# Power_section.net
KiCad netlist of a schematic drawn in Altium Designer
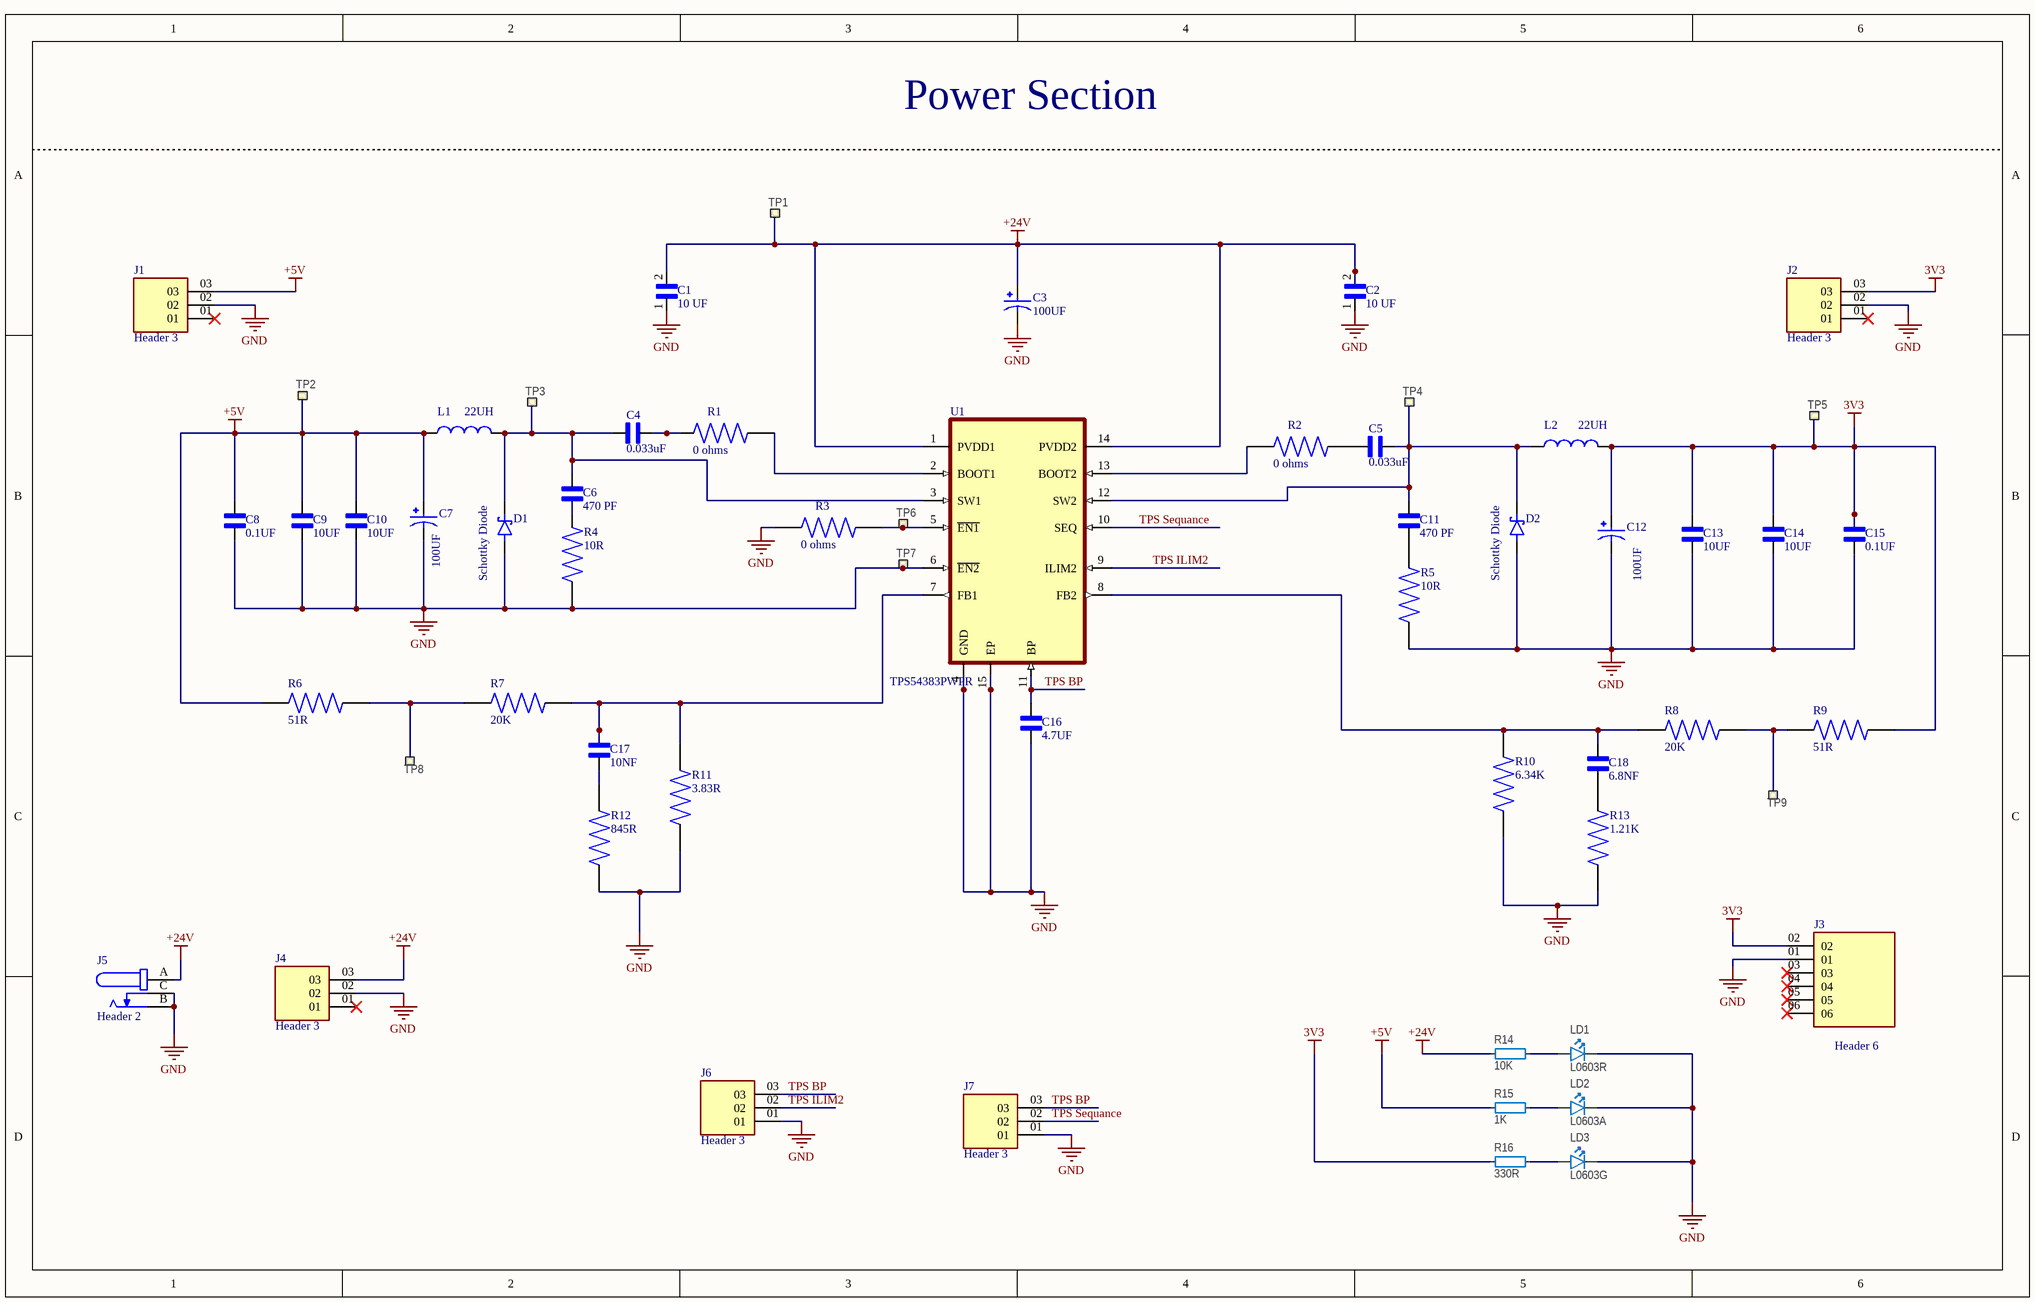
[diagram p0: Power section.SchDoc]

(export (version "E")
  (design (tool "Eeschema 10.0.6"))
  (components
    (comp (ref "C1")
      (value "10 UF")
      (footprint "CAPC3216X180N")
      (description "CAP CER 10UF 16V X5R 1206")
      (fields (field (name "MF") "TDK") (field (name "DIGI-KEY_PART_NUMBER") "445-7708-2-ND"))
      (libsource (lib "C3216X5R1E106M160AB") (part "C3216X5R1E106M160AB"))
    )
    (comp (ref "C2")
      (value "10 UF")
      (footprint "CAPC3216X180N")
      (description "CAP CER 10UF 16V X5R 1206")
      (fields (field (name "MF") "TDK") (field (name "DIGI-KEY_PART_NUMBER") "445-7708-2-ND"))
      (libsource (lib "C3216X5R1E106M160AB") (part "C3216X5R1E106M160AB"))
    )
    (comp (ref "C3")
      (value "100UF")
      (footprint "CAP_EEEFC1E101P")
      (description "Capacitor, aluminum, 25 V, ±20%, 100 μF, 0.328 x 0.390\r\ninch")
      (fields (field (name "MF") "Panasonic") (field (name "MP") "EEE-FC1E101P"))
      (libsource (lib "EEEFC1E101P") (part "EEEFC1E101P"))
    )
    (comp (ref "C4")
      (value "0.033uF")
      (footprint "CAPC1608X90")
      (description "Capacitor, ceramic, 25 V, X7R, 20%, .033 μF, 0603")
      (fields (field (name "MF") "KEMET") (field (name "MP") "C0603C104J3RACTU"))
      (libsource (lib "") (part "C0603C104J3RACTU_1"))
    )
    (comp (ref "C5")
      (value "0.033uF")
      (footprint "CAPC1608X90")
      (description "Capacitor, ceramic, 25 V, X7R, 20%, .033 μF, 0603")
      (fields (field (name "MF") "KEMET") (field (name "MP") "C0603C104J3RACTU"))
      (libsource (lib "") (part "C0603C104J3RACTU_1"))
    )
    (comp (ref "C6")
      (value "470 PF")
      (footprint "CAPC1608X90")
      (description "Capacitor, ceramic, 25 V, X7R, 20%, 470 pF, 0603")
      (fields (field (name "MF") "KEMET") (field (name "MP") "C0603C104J3RACTU"))
      (libsource (lib "Accelo Integrated_Library") (part "C0603C104J3RACTU"))
    )
    (comp (ref "C7")
      (value "100UF")
      (footprint "CAP_EEEFC1E101P")
      (description "Capacitor, aluminum, 10 V, 20%, FC series, 100 μF,\r\n0.335 x 0.374")
      (fields (field (name "MF") "Panasonic") (field (name "MP") "EEE-FC1E101P"))
      (libsource (lib "EEEFC1E101P") (part "EEEFC1E101P"))
    )
    (comp (ref "C8")
      (value "0.1UF")
      (footprint "CAPC1608X90")
      (description "Capacitor, ceramic, 10 V, X7R, 20%, 0.1 μF, 0603")
      (fields (field (name "MF") "KEMET") (field (name "MP") "C0603C104J3RACTU"))
      (libsource (lib "Accelo Integrated_Library") (part "C0603C104J3RACTU"))
    )
    (comp (ref "C9")
      (value "10UF")
      (footprint "CAPC2012X140N")
      (description "Capacitor, ceramic, 6.3 V, X5R, 20%, 10 μF, 0805")
      (fields (field (name "MF") "AVX") (field (name "MP") "0805ZD474MAT2A"))
      (libsource (lib "0805ZD474MAT2A") (part "0805ZD474MAT2A"))
    )
    (comp (ref "C10")
      (value "10UF")
      (footprint "CAPC2012X140N")
      (description "Capacitor, ceramic, 6.3 V, X5R, 20%, 10 μF, 0805")
      (fields (field (name "MF") "AVX") (field (name "MP") "0805ZD474MAT2A"))
      (libsource (lib "0805ZD474MAT2A") (part "0805ZD474MAT2A"))
    )
    (comp (ref "C11")
      (value "470 PF")
      (footprint "CAPC1608X90")
      (description "Capacitor, ceramic, 25 V, X7R, 20%, 470 pF, 0603")
      (fields (field (name "MF") "KEMET") (field (name "MP") "C0603C104J3RACTU"))
      (libsource (lib "Accelo Integrated_Library") (part "C0603C104J3RACTU"))
    )
    (comp (ref "C12")
      (value "100UF")
      (footprint "CAP_EEEFC1E101P")
      (description "Capacitor, aluminum, 10 V, 20%, FC series, 100 μF,\r\n0.335 x 0.374")
      (fields (field (name "MF") "Panasonic") (field (name "MP") "EEE-FC1E101P"))
      (libsource (lib "EEEFC1E101P") (part "EEEFC1E101P"))
    )
    (comp (ref "C13")
      (value "10UF")
      (footprint "CAPC2012X140N")
      (description "Capacitor, ceramic, 6.3 V, X5R, 20%, 10 μF, 0805")
      (fields (field (name "MF") "AVX") (field (name "MP") "0805ZD474MAT2A"))
      (libsource (lib "0805ZD474MAT2A") (part "0805ZD474MAT2A"))
    )
    (comp (ref "C14")
      (value "10UF")
      (footprint "CAPC2012X140N")
      (description "Capacitor, ceramic, 6.3 V, X5R, 20%, 10 μF, 0805")
      (fields (field (name "MF") "AVX") (field (name "MP") "0805ZD474MAT2A"))
      (libsource (lib "0805ZD474MAT2A") (part "0805ZD474MAT2A"))
    )
    (comp (ref "C15")
      (value "0.1UF")
      (footprint "CAPC1608X90")
      (description "Capacitor, ceramic, 10 V, X7R, 20%, 0.1 μF, 0603")
      (fields (field (name "MF") "KEMET") (field (name "MP") "C0603C104J3RACTU"))
      (libsource (lib "Accelo Integrated_Library") (part "C0603C104J3RACTU"))
    )
    (comp (ref "C16")
      (value "4.7UF")
      (footprint "CAPC2012X140N")
      (description "Capacitor, ceramic, 10 V, X5R, 20%, 4.7 μF, 0805")
      (fields (field (name "MF") "AVX") (field (name "MP") "0805ZD474MAT2A"))
      (libsource (lib "0805ZD474MAT2A") (part "0805ZD474MAT2A"))
    )
    (comp (ref "C17")
      (value "10NF")
      (footprint "CAPC1608X90")
      (description "Capacitor, ceramic, 25 V, X7R, 20%, 10 nF, 0603")
      (fields (field (name "MF") "KEMET") (field (name "MP") "C0603C104J3RACTU"))
      (libsource (lib "Accelo Integrated_Library") (part "C0603C104J3RACTU"))
    )
    (comp (ref "C18")
      (value "6.8NF")
      (footprint "CAPC1608X90")
      (description "Capacitor, ceramic, 25 V, X7R, 20%, 6.8 nF, 0603")
      (fields (field (name "MF") "KEMET") (field (name "MP") "C0603C104J3RACTU"))
      (libsource (lib "Accelo Integrated_Library") (part "C0603C104J3RACTU"))
    )
    (comp (ref "D1")
      (value "Schottky Diode")
      (footprint "DIOM7959X261N")
      (description "Diode Schottky 30 V 3A Surface Mount SMC")
      (fields (field (name "MF") "ON Semiconductor") (field (name "MP") "MBRS330T3G"))
      (libsource (lib "MBRS330T3G") (part "MBRS330T3G"))
    )
    (comp (ref "D2")
      (value "Schottky Diode")
      (footprint "DIOM7959X261N")
      (description "Diode Schottky 30 V 3A Surface Mount SMC")
      (fields (field (name "MF") "ON Semiconductor") (field (name "MP") "MBRS330T3G"))
      (libsource (lib "MBRS330T3G") (part "MBRS330T3G"))
    )
    (comp (ref "J1")
      (value "Header 3")
      (footprint "SAMTEC_HMTSW-103-XX-X-S-XXX")
      (description "Connector Unshrouded Header 3 Position 2.54mm Solder Straight Through Hole")
      (fields (field (name "MF") "Samtec") (field (name "MP") "HMTSW-103-10-T-S-330"))
      (libsource (lib "Accelo Integrated_Library") (part "HMTSW-103-XX-X-S-XXX"))
    )
    (comp (ref "J2")
      (value "Header 3")
      (footprint "SAMTEC_HMTSW-103-XX-X-S-XXX")
      (description "Connector Unshrouded Header 3 Position 2.54mm Solder Straight Through Hole")
      (fields (field (name "MF") "Samtec") (field (name "MP") "HMTSW-103-10-T-S-330"))
      (libsource (lib "Accelo Integrated_Library") (part "HMTSW-103-XX-X-S-XXX"))
    )
    (comp (ref "J3")
      (value "Header 6")
      (footprint "SAMTEC_MTLW-106-06-G-S-180")
      (fields (field (name "MP") "MTLW-106-06-G-S-180"))
      (libsource (lib "MTLW-106-06-G-S-180") (part "MTLW-106-06-G-S-180"))
    )
    (comp (ref "J4")
      (value "Header 3")
      (footprint "SAMTEC_HMTSW-103-XX-X-S-XXX")
      (description "Connector Unshrouded Header 3 Position 2.54mm Solder Straight Through Hole")
      (fields (field (name "MF") "Samtec") (field (name "MP") "HMTSW-103-10-T-S-330"))
      (libsource (lib "Accelo Integrated_Library") (part "HMTSW-103-XX-X-S-XXX"))
    )
    (comp (ref "J5")
      (value "Header 2")
      (footprint "TENSILITY_54-00129")
      (description "Connector, dc jack 5.5x2.1 mm, PCB mount, 90 degrees, silver plated, thru hole")
      (fields (field (name "MF") "Tensility International Corp") (field (name "MP") "54-00129"))
      (libsource (lib "54-00129") (part "54-00129"))
    )
    (comp (ref "J6")
      (value "Header 3")
      (footprint "SAMTEC_HMTSW-103-XX-X-S-XXX")
      (description "Connector Unshrouded Header 3 Position 2.54mm Solder Straight Through Hole")
      (fields (field (name "MF") "Samtec") (field (name "MP") "HMTSW-103-10-T-S-330"))
      (libsource (lib "Accelo Integrated_Library") (part "HMTSW-103-XX-X-S-XXX"))
    )
    (comp (ref "J7")
      (value "Header 3")
      (footprint "SAMTEC_HMTSW-103-XX-X-S-XXX")
      (description "Connector Unshrouded Header 3 Position 2.54mm Solder Straight Through Hole")
      (fields (field (name "MF") "Samtec") (field (name "MP") "HMTSW-103-10-T-S-330"))
      (libsource (lib "Accelo Integrated_Library") (part "HMTSW-103-XX-X-S-XXX"))
    )
    (comp (ref "L1")
      (value "22UH")
      (footprint "IND_MSS1278-223MLB")
      (description "Inductor, Power, 6.8 A, 0.038 Ω, 22 μH, 0.484 x 0.484\r\ninch")
      (fields (field (name "MF") "Coilcraft") (field (name "MP") "MSS1278-223MLB"))
      (libsource (lib "MSS1278-223MLB") (part "MSS1278-223MLB"))
    )
    (comp (ref "L2")
      (value "22UH")
      (footprint "IND_MSS1278-223MLB")
      (description "Inductor, Power, 6.8 A, 0.038 Ω, 22 μH, 0.484 x 0.484\r\ninch")
      (fields (field (name "MF") "Coilcraft") (field (name "MP") "MSS1278-223MLB"))
      (libsource (lib "MSS1278-223MLB") (part "MSS1278-223MLB"))
    )
    (comp (ref "LD1")
      (value "L0603R")
      (footprint "LED_0603_R")
      (description "LED, Red, 0603, Vf=2V, - 40 to +100°C")
      (fields
        (field (name "PART NUMBER") "ASMT-RR45-AQ902")
        (field (name "MANUFACTURER") "Avago")
        (field (name "AUTHOR") "rsk")
      )
      (libsource (lib "pca10152") (part "ASMT-RR45-AQ902"))
    )
    (comp (ref "LD2")
      (value "L0603A")
      (footprint "LED_0603_Y")
      (description "LED, Amber, 0603,  Vf=2V, - 40 to +100°C")
      (fields
        (field (name "PART NUMBER") "ASMT-RA45-AP932")
        (field (name "MANUFACTURER") "Avago")
        (field (name "AUTHOR") "rsk")
      )
      (libsource (lib "pca10152") (part "ASMT-RA45-AP932"))
    )
    (comp (ref "LD3")
      (value "L0603G")
      (footprint "LED_0603_G")
      (description "LED, Yellow Green, 0603, Vf=2V, - 40 to +100°C")
      (fields
        (field (name "PART NUMBER") "ASMT-RF45-AN002")
        (field (name "MANUFACTURER") "Avago")
        (field (name "AUTHOR") "rsk")
      )
      (libsource (lib "pca10152") (part "ASMT-RF45-AN002"))
    )
    (comp (ref "R1")
      (value "0 ohms")
      (footprint "RESC1608X55N")
      (description "Resistor, chip, 1/16 W, 5%, 0 Ω, 0603")
      (fields (field (name "MF") "Yageo") (field (name "MP") "RC0603JR-0751RL"))
      (libsource (lib "RC0603JR-0751RL") (part "RC0603JR-0751RL"))
    )
    (comp (ref "R2")
      (value "0 ohms")
      (footprint "RESC1608X55N")
      (description "Resistor, chip, 1/16 W, 5%, 0 Ω, 0603")
      (fields (field (name "MF") "Yageo") (field (name "MP") "RC0603JR-0751RL"))
      (libsource (lib "RC0603JR-0751RL") (part "RC0603JR-0751RL"))
    )
    (comp (ref "R3")
      (value "0 ohms")
      (footprint "RESC1608X55N")
      (description "Resistor, chip, 1/16 W, 5%, 0 Ω, 0603")
      (fields (field (name "MF") "Yageo") (field (name "MP") "RC0603JR-0751RL"))
      (libsource (lib "RC0603JR-0751RL") (part "RC0603JR-0751RL"))
    )
    (comp (ref "R4")
      (value "10R")
      (footprint "RESC1608X55N")
      (description "Resistor, chip, 1/16 W, 5%, 10 Ω, 0603")
      (fields (field (name "MF") "Yageo") (field (name "MP") "RC0603JR-0751RL"))
      (libsource (lib "RC0603JR-0751RL") (part "RC0603JR-0751RL"))
    )
    (comp (ref "R5")
      (value "10R")
      (footprint "RESC1608X55N")
      (description "Resistor, chip, 1/16 W, 5%, 10 Ω, 0603")
      (fields (field (name "MF") "Yageo") (field (name "MP") "RC0603JR-0751RL"))
      (libsource (lib "RC0603JR-0751RL") (part "RC0603JR-0751RL"))
    )
    (comp (ref "R6")
      (value "51R")
      (footprint "RESC1608X55N")
      (description "Resistor, chip, 1/16 W, 5%, 51 Ω, 0603")
      (fields (field (name "MF") "Yageo") (field (name "MP") "RC0603JR-0751RL"))
      (libsource (lib "RC0603JR-0751RL") (part "RC0603JR-0751RL"))
    )
    (comp (ref "R7")
      (value "20K")
      (footprint "RESC1608X55N")
      (description "Resistor, chip, 1/16 W, 1%, 20 kΩ, 0603")
      (fields (field (name "MF") "Yageo") (field (name "MP") "RC0603JR-0751RL"))
      (libsource (lib "RC0603JR-0751RL") (part "RC0603JR-0751RL"))
    )
    (comp (ref "R8")
      (value "20K")
      (footprint "RESC1608X55N")
      (description "Resistor, chip, 1/16 W, 1%, 20 kΩ, 0603")
      (fields (field (name "MF") "Yageo") (field (name "MP") "RC0603JR-0751RL"))
      (libsource (lib "RC0603JR-0751RL") (part "RC0603JR-0751RL"))
    )
    (comp (ref "R9")
      (value "51R")
      (footprint "RESC1608X55N")
      (description "Resistor, chip, 1/16 W, 5%, 51 Ω, 0603")
      (fields (field (name "MF") "Yageo") (field (name "MP") "RC0603JR-0751RL"))
      (libsource (lib "RC0603JR-0751RL") (part "RC0603JR-0751RL"))
    )
    (comp (ref "R10")
      (value "6.34K")
      (footprint "RESC1608X55N")
      (description "Resistor, chip, 1/16 W, 1%, 6.34 kΩ, 0603")
      (fields (field (name "MF") "Yageo") (field (name "MP") "RC0603JR-0751RL"))
      (libsource (lib "RC0603JR-0751RL") (part "RC0603JR-0751RL"))
    )
    (comp (ref "R11")
      (value "3.83R")
      (footprint "RESC1608X55N")
      (description "Resistor, chip, 1/16 W, 1%, 3.83 kΩ, 0603")
      (fields (field (name "MF") "Yageo") (field (name "MP") "RC0603JR-0751RL"))
      (libsource (lib "RC0603JR-0751RL") (part "RC0603JR-0751RL"))
    )
    (comp (ref "R12")
      (value "845R")
      (footprint "RESC1608X55N")
      (description "Resistor, chip, 1/16 W, 1%, 845 Ω, 0603")
      (fields (field (name "MF") "Yageo") (field (name "MP") "RC0603JR-0751RL"))
      (libsource (lib "RC0603JR-0751RL") (part "RC0603JR-0751RL"))
    )
    (comp (ref "R13")
      (value "1.21K")
      (footprint "RESC1608X55N")
      (description "Resistor, chip, 1/16 W, 1%, 1.21 kΩ, 0603")
      (fields (field (name "MF") "Yageo") (field (name "MP") "RC0603JR-0751RL"))
      (libsource (lib "RC0603JR-0751RL") (part "RC0603JR-0751RL"))
    )
    (comp (ref "R14")
      (value "10K")
      (footprint "RESC0603X03L_C")
      (description "Resistor, ±1%, 0.05W")
      (fields
        (field (name "PART NUMBER") "R0201-1k0")
        (field (name "MANUFACTURER") "N.A.")
        (field (name "AUTHOR") "rsk")
      )
      (libsource (lib "pca10152") (part "R0201-1k0"))
    )
    (comp (ref "R15")
      (value "1K")
      (footprint "RESC0603X03L_C")
      (description "Resistor, ±1%, 0.05W")
      (fields
        (field (name "PART NUMBER") "R0201-1k0")
        (field (name "MANUFACTURER") "N.A.")
        (field (name "AUTHOR") "rsk")
      )
      (libsource (lib "pca10152") (part "R0201-1k0"))
    )
    (comp (ref "R16")
      (value "330R")
      (footprint "RESC0603X03L_C")
      (description "Resistor, ±1%, 0.05W")
      (fields
        (field (name "PART NUMBER") "R0201-1k0")
        (field (name "MANUFACTURER") "N.A.")
        (field (name "AUTHOR") "rsk")
      )
      (libsource (lib "pca10152") (part "R0201-1k0"))
    )
    (comp (ref "TP1")
      (value "Ø0.7mm,SMD")
      (footprint "TP_SMD_D0.7mm")
      (description "0.7mm circular SMD testpad")
      (fields
        (field (name "PART NUMBER") "TP_SMD_Ø0.7MM")
        (field (name "MANUFACTURER") "Nordic Semiconductor")
        (field (name "AUTHOR") "rsk")
      )
      (libsource (lib "") (part "TP_SMD_Ø0.7MM_1"))
    )
    (comp (ref "TP2")
      (value "Ø0.7mm,SMD")
      (footprint "TP_SMD_D0.7mm")
      (description "0.7mm circular SMD testpad")
      (fields
        (field (name "PART NUMBER") "TP_SMD_Ø0.7MM")
        (field (name "MANUFACTURER") "Nordic Semiconductor")
        (field (name "AUTHOR") "rsk")
      )
      (libsource (lib "") (part "TP_SMD_Ø0.7MM_1"))
    )
    (comp (ref "TP3")
      (value "Ø0.7mm,SMD")
      (footprint "TP_SMD_D0.7mm")
      (description "0.7mm circular SMD testpad")
      (fields
        (field (name "PART NUMBER") "TP_SMD_Ø0.7MM")
        (field (name "MANUFACTURER") "Nordic Semiconductor")
        (field (name "AUTHOR") "rsk")
      )
      (libsource (lib "") (part "TP_SMD_Ø0.7MM_1"))
    )
    (comp (ref "TP4")
      (value "Ø0.7mm,SMD")
      (footprint "TP_SMD_D0.7mm")
      (description "0.7mm circular SMD testpad")
      (fields
        (field (name "PART NUMBER") "TP_SMD_Ø0.7MM")
        (field (name "MANUFACTURER") "Nordic Semiconductor")
        (field (name "AUTHOR") "rsk")
      )
      (libsource (lib "") (part "TP_SMD_Ø0.7MM_1"))
    )
    (comp (ref "TP5")
      (value "Ø0.7mm,SMD")
      (footprint "TP_SMD_D0.7mm")
      (description "0.7mm circular SMD testpad")
      (fields
        (field (name "PART NUMBER") "TP_SMD_Ø0.7MM")
        (field (name "MANUFACTURER") "Nordic Semiconductor")
        (field (name "AUTHOR") "rsk")
      )
      (libsource (lib "") (part "TP_SMD_Ø0.7MM_1"))
    )
    (comp (ref "TP6")
      (value "Ø0.7mm,SMD")
      (footprint "TP_SMD_D0.7mm")
      (description "0.7mm circular SMD testpad")
      (fields
        (field (name "PART NUMBER") "TP_SMD_Ø0.7MM")
        (field (name "MANUFACTURER") "Nordic Semiconductor")
        (field (name "AUTHOR") "rsk")
      )
      (libsource (lib "") (part "TP_SMD_Ø0.7MM_1"))
    )
    (comp (ref "TP7")
      (value "Ø0.7mm,SMD")
      (footprint "TP_SMD_D0.7mm")
      (description "0.7mm circular SMD testpad")
      (fields
        (field (name "PART NUMBER") "TP_SMD_Ø0.7MM")
        (field (name "MANUFACTURER") "Nordic Semiconductor")
        (field (name "AUTHOR") "rsk")
      )
      (libsource (lib "") (part "TP_SMD_Ø0.7MM_1"))
    )
    (comp (ref "TP8")
      (value "Ø0.7mm,SMD")
      (footprint "TP_SMD_D0.7mm")
      (description "0.7mm circular SMD testpad")
      (fields
        (field (name "PART NUMBER") "TP_SMD_Ø0.7MM")
        (field (name "MANUFACTURER") "Nordic Semiconductor")
        (field (name "AUTHOR") "rsk")
      )
      (libsource (lib "pca10152") (part "TP_SMD_Ø0.7MM"))
    )
    (comp (ref "TP9")
      (value "Ø0.7mm,SMD")
      (footprint "TP_SMD_D0.7mm")
      (description "0.7mm circular SMD testpad")
      (fields
        (field (name "PART NUMBER") "TP_SMD_Ø0.7MM")
        (field (name "MANUFACTURER") "Nordic Semiconductor")
        (field (name "AUTHOR") "rsk")
      )
      (libsource (lib "pca10152") (part "TP_SMD_Ø0.7MM"))
    )
    (comp (ref "U1")
      (value "TPS54383PWPR")
      (footprint "IC_TPS27S100BPWPR")
      (fields (field (name "MF") "{'manufacturer': u'Texas Instruments'}"))
      (libsource (lib "TP") (part "TPS54383PWPR"))
    )
  )
  (nets
    (net (code "1") (name "+5V") (class "Default")
      (node (ref "C10") (pin "1") (pinfunction "1_1") (pintype "passive"))
      (node (ref "C7") (pin "1") (pinfunction "1_1") (pintype "passive"))
      (node (ref "C8") (pin "1") (pinfunction "1_1") (pintype "passive"))
      (node (ref "C9") (pin "1") (pinfunction "1_1") (pintype "passive"))
      (node (ref "J1") (pin "03") (pinfunction "03_03") (pintype "passive"))
      (node (ref "L1") (pin "1") (pinfunction "1_1") (pintype "passive"))
      (node (ref "R15") (pin "1") (pinfunction "1_1") (pintype "passive"))
      (node (ref "R6") (pin "2") (pinfunction "2_2") (pintype "passive"))
      (node (ref "TP2") (pin "1") (pinfunction "1_1") (pintype "passive"))
    )
    (net (code "2") (name "+24V") (class "Default")
      (node (ref "C1") (pin "2") (pinfunction "2_2") (pintype "passive"))
      (node (ref "C2") (pin "2") (pinfunction "2_2") (pintype "passive"))
      (node (ref "C3") (pin "1") (pinfunction "1_1") (pintype "passive"))
      (node (ref "J4") (pin "03") (pinfunction "03_03") (pintype "passive"))
      (node (ref "J5") (pin "A") (pinfunction "A_A") (pintype "passive"))
      (node (ref "R14") (pin "1") (pinfunction "1_1") (pintype "passive"))
      (node (ref "TP1") (pin "1") (pinfunction "1_1") (pintype "passive"))
      (node (ref "U1") (pin "1") (pinfunction "PVDD1_1") (pintype "power_in"))
      (node (ref "U1") (pin "14") (pinfunction "PVDD2_14") (pintype "power_in"))
    )
    (net (code "3") (name "/TPS BP") (class "Default")
      (node (ref "C16") (pin "1") (pinfunction "1_1") (pintype "passive"))
      (node (ref "J6") (pin "03") (pinfunction "03_03") (pintype "passive"))
      (node (ref "J7") (pin "03") (pinfunction "03_03") (pintype "passive"))
      (node (ref "U1") (pin "11") (pinfunction "BP_11") (pintype "input"))
    )
    (net (code "4") (name "/TPS ILIM2") (class "Default")
      (node (ref "J6") (pin "02") (pinfunction "02_02") (pintype "passive"))
      (node (ref "U1") (pin "9") (pinfunction "ILIM2_9") (pintype "input"))
    )
    (net (code "5") (name "/TPS Sequance") (class "Default")
      (node (ref "J7") (pin "02") (pinfunction "02_02") (pintype "passive"))
      (node (ref "U1") (pin "10") (pinfunction "SEQ_10") (pintype "input"))
    )
    (net (code "6") (name "3V3") (class "Default")
      (node (ref "C12") (pin "1") (pinfunction "1_1") (pintype "passive"))
      (node (ref "C13") (pin "1") (pinfunction "1_1") (pintype "passive"))
      (node (ref "C14") (pin "1") (pinfunction "1_1") (pintype "passive"))
      (node (ref "C15") (pin "1") (pinfunction "1_1") (pintype "passive"))
      (node (ref "J2") (pin "03") (pinfunction "03_03") (pintype "passive"))
      (node (ref "J3") (pin "02") (pinfunction "02_02") (pintype "passive"))
      (node (ref "L2") (pin "2") (pinfunction "2_2") (pintype "passive"))
      (node (ref "R16") (pin "1") (pinfunction "1_1") (pintype "passive"))
      (node (ref "R9") (pin "1") (pinfunction "1_1") (pintype "passive"))
      (node (ref "TP5") (pin "1") (pinfunction "1_1") (pintype "passive"))
    )
    (net (code "7") (name "GND") (class "Default")
      (node (ref "C1") (pin "1") (pinfunction "1_1") (pintype "passive"))
      (node (ref "C10") (pin "2") (pinfunction "2_2") (pintype "passive"))
      (node (ref "C12") (pin "2") (pinfunction "2_2") (pintype "passive"))
      (node (ref "C13") (pin "2") (pinfunction "2_2") (pintype "passive"))
      (node (ref "C14") (pin "2") (pinfunction "2_2") (pintype "passive"))
      (node (ref "C15") (pin "2") (pinfunction "2_2") (pintype "passive"))
      (node (ref "C16") (pin "2") (pinfunction "2_2") (pintype "passive"))
      (node (ref "C2") (pin "1") (pinfunction "1_1") (pintype "passive"))
      (node (ref "C3") (pin "2") (pinfunction "2_2") (pintype "passive"))
      (node (ref "C7") (pin "2") (pinfunction "2_2") (pintype "passive"))
      (node (ref "C8") (pin "2") (pinfunction "2_2") (pintype "passive"))
      (node (ref "C9") (pin "2") (pinfunction "2_2") (pintype "passive"))
      (node (ref "D1") (pin "A") (pinfunction "A_A") (pintype "passive"))
      (node (ref "D2") (pin "A") (pinfunction "A_A") (pintype "passive"))
      (node (ref "J1") (pin "02") (pinfunction "02_02") (pintype "passive"))
      (node (ref "J2") (pin "02") (pinfunction "02_02") (pintype "passive"))
      (node (ref "J3") (pin "01") (pinfunction "01_01") (pintype "passive"))
      (node (ref "J4") (pin "02") (pinfunction "02_02") (pintype "passive"))
      (node (ref "J5") (pin "B") (pinfunction "B_B") (pintype "passive"))
      (node (ref "J5") (pin "C") (pinfunction "C_C") (pintype "passive"))
      (node (ref "J6") (pin "01") (pinfunction "01_01") (pintype "passive"))
      (node (ref "J7") (pin "01") (pinfunction "01_01") (pintype "passive"))
      (node (ref "LD1") (pin "1") (pinfunction "C_1") (pintype "passive"))
      (node (ref "LD2") (pin "1") (pinfunction "C_1") (pintype "passive"))
      (node (ref "LD3") (pin "1") (pinfunction "C_1") (pintype "passive"))
      (node (ref "R10") (pin "1") (pinfunction "1_1") (pintype "passive"))
      (node (ref "R11") (pin "1") (pinfunction "1_1") (pintype "passive"))
      (node (ref "R12") (pin "1") (pinfunction "1_1") (pintype "passive"))
      (node (ref "R13") (pin "1") (pinfunction "1_1") (pintype "passive"))
      (node (ref "R3") (pin "1") (pinfunction "1_1") (pintype "passive"))
      (node (ref "R4") (pin "1") (pinfunction "1_1") (pintype "passive"))
      (node (ref "R5") (pin "1") (pinfunction "1_1") (pintype "passive"))
      (node (ref "TP7") (pin "1") (pinfunction "1_1") (pintype "passive"))
      (node (ref "U1") (pin "15") (pinfunction "EP_15") (pintype "power_in"))
      (node (ref "U1") (pin "4") (pinfunction "GND_4") (pintype "power_in"))
      (node (ref "U1") (pin "6") (pinfunction "~{EN2}_6") (pintype "input"))
    )
    (net (code "8") (name "Net-(C4-Pad1)") (class "Default")
      (node (ref "C4") (pin "1") (pinfunction "1_1") (pintype "passive"))
      (node (ref "R1") (pin "1") (pinfunction "1_1") (pintype "passive"))
    )
    (net (code "9") (name "Net-(C5-Pad2)") (class "Default")
      (node (ref "C5") (pin "2") (pinfunction "2_2") (pintype "passive"))
      (node (ref "R2") (pin "2") (pinfunction "2_2") (pintype "passive"))
    )
    (net (code "10") (name "Net-(C6-Pad2)") (class "Default")
      (node (ref "C6") (pin "2") (pinfunction "2_2") (pintype "passive"))
      (node (ref "R4") (pin "2") (pinfunction "2_2") (pintype "passive"))
    )
    (net (code "11") (name "Net-(C11-Pad2)") (class "Default")
      (node (ref "C11") (pin "2") (pinfunction "2_2") (pintype "passive"))
      (node (ref "R5") (pin "2") (pinfunction "2_2") (pintype "passive"))
    )
    (net (code "12") (name "Net-(C17-Pad2)") (class "Default")
      (node (ref "C17") (pin "2") (pinfunction "2_2") (pintype "passive"))
      (node (ref "R12") (pin "2") (pinfunction "2_2") (pintype "passive"))
    )
    (net (code "13") (name "Net-(C18-Pad2)") (class "Default")
      (node (ref "C18") (pin "2") (pinfunction "2_2") (pintype "passive"))
      (node (ref "R13") (pin "2") (pinfunction "2_2") (pintype "passive"))
    )
    (net (code "14") (name "Net-(D1-K)") (class "Default")
      (node (ref "C4") (pin "2") (pinfunction "2_2") (pintype "passive"))
      (node (ref "C6") (pin "1") (pinfunction "1_1") (pintype "passive"))
      (node (ref "D1") (pin "C") (pinfunction "K_C") (pintype "passive"))
      (node (ref "L1") (pin "2") (pinfunction "2_2") (pintype "passive"))
      (node (ref "TP3") (pin "1") (pinfunction "1_1") (pintype "passive"))
      (node (ref "U1") (pin "3") (pinfunction "SW1_3") (pintype "input"))
    )
    (net (code "15") (name "Net-(D2-K)") (class "Default")
      (node (ref "C11") (pin "1") (pinfunction "1_1") (pintype "passive"))
      (node (ref "C5") (pin "1") (pinfunction "1_1") (pintype "passive"))
      (node (ref "D2") (pin "C") (pinfunction "K_C") (pintype "passive"))
      (node (ref "L2") (pin "1") (pinfunction "1_1") (pintype "passive"))
      (node (ref "TP4") (pin "1") (pinfunction "1_1") (pintype "passive"))
      (node (ref "U1") (pin "12") (pinfunction "SW2_12") (pintype "input"))
    )
    (net (code "16") (name "Net-(LD1-A)") (class "Default")
      (node (ref "LD1") (pin "2") (pinfunction "A_2") (pintype "passive"))
      (node (ref "R14") (pin "2") (pinfunction "2_2") (pintype "passive"))
    )
    (net (code "17") (name "Net-(LD2-A)") (class "Default")
      (node (ref "LD2") (pin "2") (pinfunction "A_2") (pintype "passive"))
      (node (ref "R15") (pin "2") (pinfunction "2_2") (pintype "passive"))
    )
    (net (code "18") (name "Net-(LD3-A)") (class "Default")
      (node (ref "LD3") (pin "2") (pinfunction "A_2") (pintype "passive"))
      (node (ref "R16") (pin "2") (pinfunction "2_2") (pintype "passive"))
    )
    (net (code "19") (name "Net-(R6-Pad1)") (class "Default")
      (node (ref "R6") (pin "1") (pinfunction "1_1") (pintype "passive"))
      (node (ref "R7") (pin "2") (pinfunction "2_2") (pintype "passive"))
      (node (ref "TP8") (pin "1") (pinfunction "1_1") (pintype "passive"))
    )
    (net (code "20") (name "Net-(R8-Pad1)") (class "Default")
      (node (ref "R8") (pin "1") (pinfunction "1_1") (pintype "passive"))
      (node (ref "R9") (pin "2") (pinfunction "2_2") (pintype "passive"))
      (node (ref "TP9") (pin "1") (pinfunction "1_1") (pintype "passive"))
    )
    (net (code "21") (name "Net-(U1-BOOT1)") (class "Default")
      (node (ref "R1") (pin "2") (pinfunction "2_2") (pintype "passive"))
      (node (ref "U1") (pin "2") (pinfunction "BOOT1_2") (pintype "input"))
    )
    (net (code "22") (name "Net-(U1-BOOT2)") (class "Default")
      (node (ref "R2") (pin "1") (pinfunction "1_1") (pintype "passive"))
      (node (ref "U1") (pin "13") (pinfunction "BOOT2_13") (pintype "input"))
    )
    (net (code "23") (name "Net-(U1-FB1)") (class "Default")
      (node (ref "C17") (pin "1") (pinfunction "1_1") (pintype "passive"))
      (node (ref "R11") (pin "2") (pinfunction "2_2") (pintype "passive"))
      (node (ref "R7") (pin "1") (pinfunction "1_1") (pintype "passive"))
      (node (ref "U1") (pin "7") (pinfunction "FB1_7") (pintype "output"))
    )
    (net (code "24") (name "Net-(U1-FB2)") (class "Default")
      (node (ref "C18") (pin "1") (pinfunction "1_1") (pintype "passive"))
      (node (ref "R10") (pin "2") (pinfunction "2_2") (pintype "passive"))
      (node (ref "R8") (pin "2") (pinfunction "2_2") (pintype "passive"))
      (node (ref "U1") (pin "8") (pinfunction "FB2_8") (pintype "output"))
    )
    (net (code "25") (name "Net-(U1-~{EN1})") (class "Default")
      (node (ref "R3") (pin "2") (pinfunction "2_2") (pintype "passive"))
      (node (ref "TP6") (pin "1") (pinfunction "1_1") (pintype "passive"))
      (node (ref "U1") (pin "5") (pinfunction "~{EN1}_5") (pintype "input"))
    )
    (net (code "26") (name "unconnected-(J1-Pad01)") (class "Default")
      (node (ref "J1") (pin "01") (pinfunction "01_01") (pintype "passive+no_connect"))
    )
    (net (code "27") (name "unconnected-(J2-Pad01)") (class "Default")
      (node (ref "J2") (pin "01") (pinfunction "01_01") (pintype "passive+no_connect"))
    )
    (net (code "28") (name "unconnected-(J3-Pad03)") (class "Default")
      (node (ref "J3") (pin "03") (pinfunction "03_03") (pintype "passive+no_connect"))
    )
    (net (code "29") (name "unconnected-(J3-Pad04)") (class "Default")
      (node (ref "J3") (pin "04") (pinfunction "04_04") (pintype "passive+no_connect"))
    )
    (net (code "30") (name "unconnected-(J3-Pad05)") (class "Default")
      (node (ref "J3") (pin "05") (pinfunction "05_05") (pintype "passive+no_connect"))
    )
    (net (code "31") (name "unconnected-(J3-Pad06)") (class "Default")
      (node (ref "J3") (pin "06") (pinfunction "06_06") (pintype "passive+no_connect"))
    )
    (net (code "32") (name "unconnected-(J4-Pad01)") (class "Default")
      (node (ref "J4") (pin "01") (pinfunction "01_01") (pintype "passive+no_connect"))
    )
  )
)
